# 0122-lion-charger.net
KiCad netlist of a schematic drawn in EAGLE
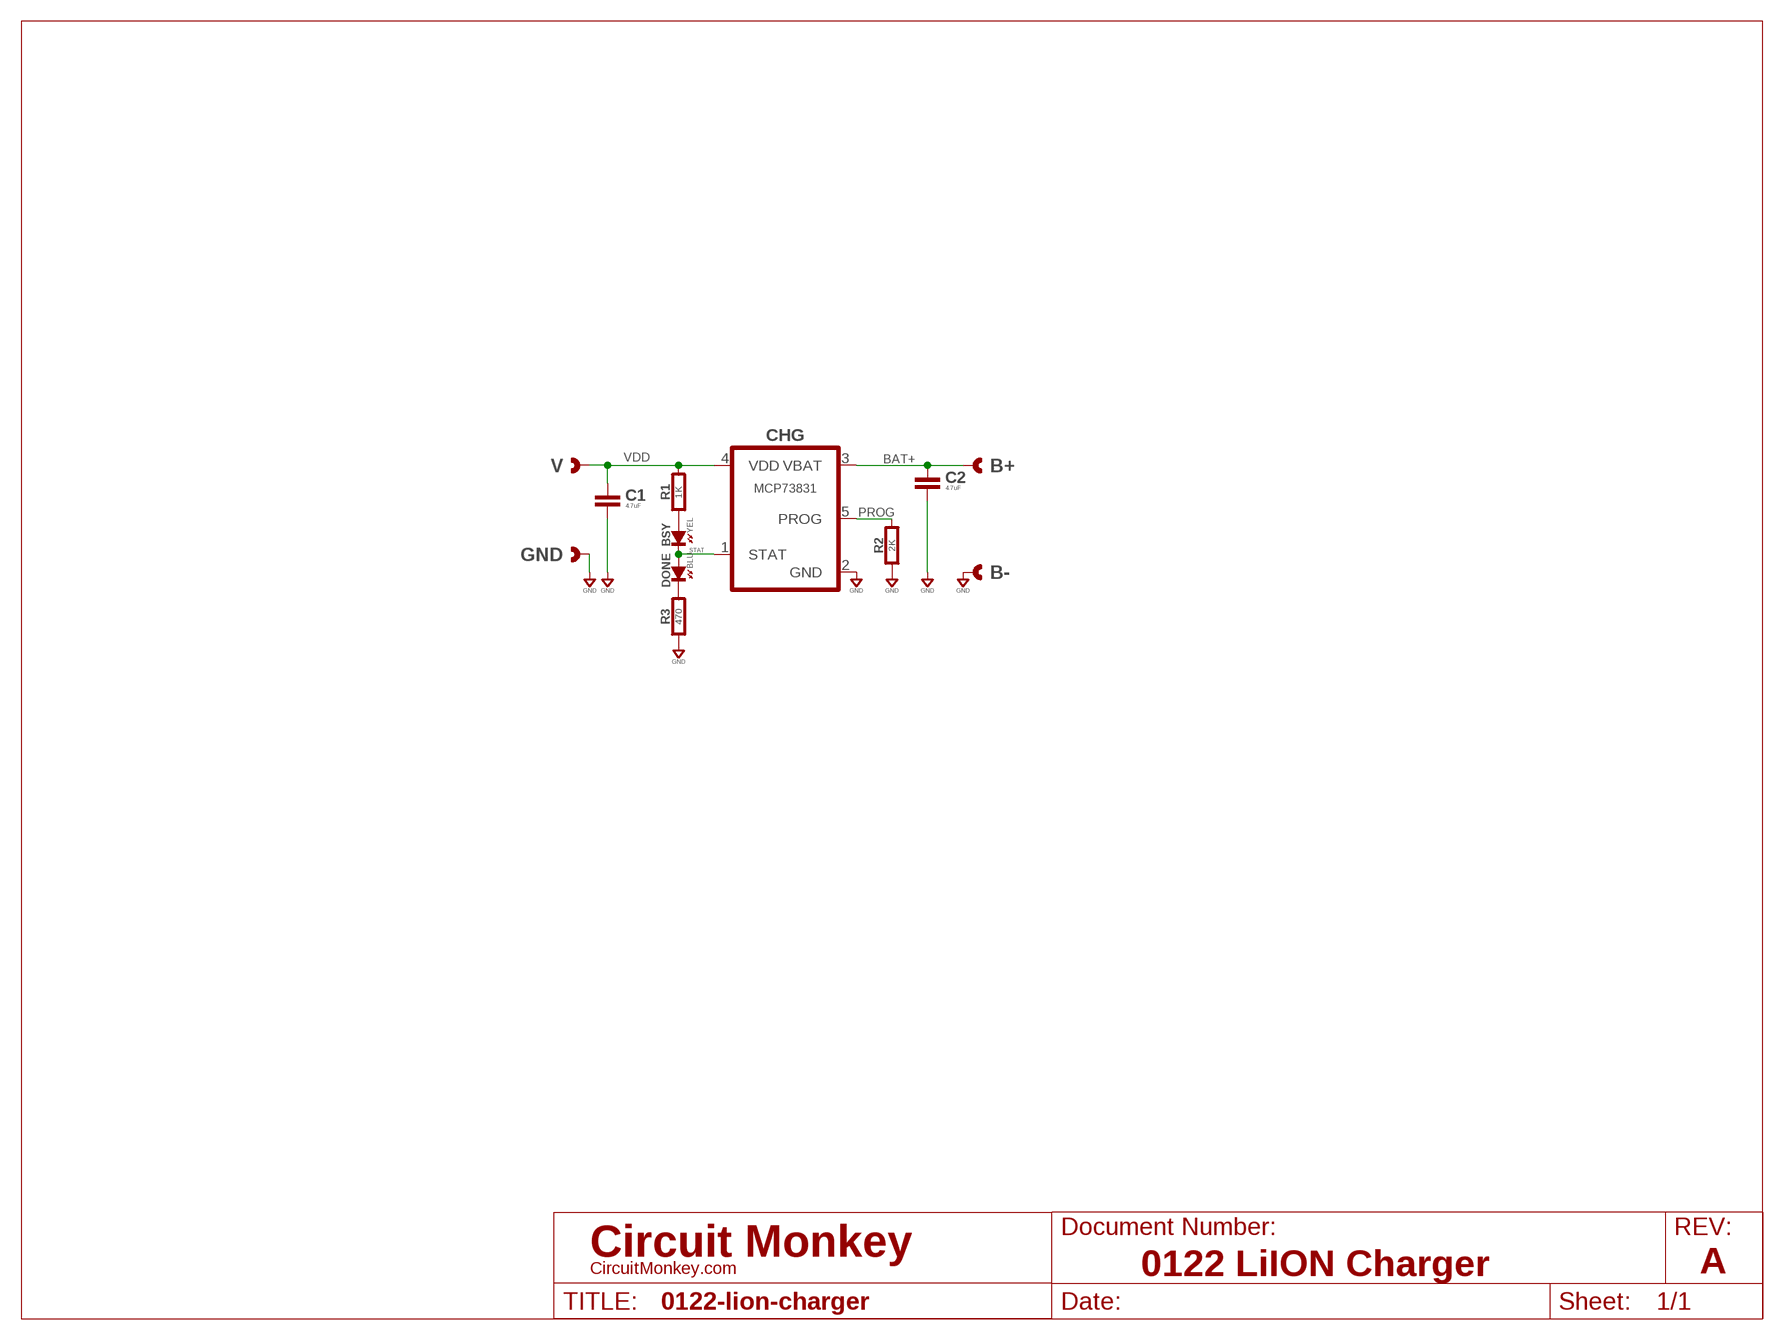
[diagram p0: schematic, sheet 1]

(export (version "E")
  (design (tool "Eeschema 10.0.6"))
  (components
    (comp (ref "B+")
      (value "CAST-01X12.00MM")
      (footprint "eagle-import:CAST01-2.00MM")
      (libsource (lib "eagle-import") (part "CAST-01X12.00MM"))
    )
    (comp (ref "B-")
      (value "CAST-01X12.00MM")
      (footprint "eagle-import:CAST01-2.00MM")
      (libsource (lib "eagle-import") (part "CAST-01X12.00MM"))
    )
    (comp (ref "BSY")
      (value "YEL")
      (footprint "eagle-import:SMD_0603")
      (libsource (lib "eagle-import") (part "SMT0603"))
    )
    (comp (ref "C1")
      (value "4.7uF")
      (footprint "eagle-import:0603-CAP")
      (libsource (lib "eagle-import") (part "CAPACITOR0603"))
    )
    (comp (ref "C2")
      (value "4.7uF")
      (footprint "eagle-import:0603-CAP")
      (libsource (lib "eagle-import") (part "CAPACITOR0603"))
    )
    (comp (ref "CHG")
      (value "MCP73831")
      (footprint "eagle-import:SOT-23-5")
      (fields (field (name "MFR") "Microchip") (field (name "MPN") "MCP73831-2ACI/OT"))
      (libsource (lib "eagle-import") (part "MCP73831/2-SOT23-5"))
    )
    (comp (ref "DONE")
      (value "BLU")
      (footprint "eagle-import:SMD_0603")
      (libsource (lib "eagle-import") (part "SMT0603"))
    )
    (comp (ref "GND")
      (value "CAST-01X12.00MM")
      (footprint "eagle-import:CAST01-2.00MM")
      (libsource (lib "eagle-import") (part "CAST-01X12.00MM"))
    )
    (comp (ref "R1")
      (value "1K")
      (footprint "eagle-import:0603-RES")
      (libsource (lib "eagle-import") (part "RESISTOR0603"))
    )
    (comp (ref "R2")
      (value "2K")
      (footprint "eagle-import:0603-RES")
      (libsource (lib "eagle-import") (part "RESISTOR0603"))
    )
    (comp (ref "R3")
      (value "470")
      (footprint "eagle-import:0603-RES")
      (libsource (lib "eagle-import") (part "RESISTOR0603"))
    )
    (comp (ref "V")
      (value "CAST-01X12.00MM")
      (footprint "eagle-import:CAST01-2.00MM")
      (libsource (lib "eagle-import") (part "CAST-01X12.00MM"))
    )
  )
  (nets
    (net (code "1") (name "/BAT+") (class "Default")
      (node (ref "B+") (pin "1") (pinfunction "1_1") (pintype "bidirectional"))
      (node (ref "B+") (pin "P$1") (pinfunction "1_P$1") (pintype "bidirectional"))
      (node (ref "B+") (pin "P$2") (pinfunction "1_P$2") (pintype "bidirectional"))
      (node (ref "C2") (pin "1") (pinfunction "1_1") (pintype "passive"))
      (node (ref "CHG") (pin "3") (pinfunction "VBAT_3") (pintype "bidirectional"))
    )
    (net (code "2") (name "/PROG") (class "Default")
      (node (ref "CHG") (pin "5") (pinfunction "PROG_5") (pintype "bidirectional"))
      (node (ref "R2") (pin "2") (pinfunction "2_2") (pintype "passive"))
    )
    (net (code "3") (name "/STAT") (class "Default")
      (node (ref "BSY") (pin "K") (pinfunction "C_K") (pintype "passive"))
      (node (ref "CHG") (pin "1") (pinfunction "STAT_1") (pintype "bidirectional"))
      (node (ref "DONE") (pin "A") (pinfunction "A_A") (pintype "passive"))
    )
    (net (code "4") (name "/VDD") (class "Default")
      (node (ref "C1") (pin "1") (pinfunction "1_1") (pintype "passive"))
      (node (ref "CHG") (pin "4") (pinfunction "VDD_4") (pintype "bidirectional"))
      (node (ref "R1") (pin "2") (pinfunction "2_2") (pintype "passive"))
      (node (ref "V") (pin "1") (pinfunction "1_1") (pintype "bidirectional"))
      (node (ref "V") (pin "P$1") (pinfunction "1_P$1") (pintype "bidirectional"))
      (node (ref "V") (pin "P$2") (pinfunction "1_P$2") (pintype "bidirectional"))
    )
    (net (code "5") (name "GND") (class "Default")
      (node (ref "B-") (pin "1") (pinfunction "1_1") (pintype "bidirectional"))
      (node (ref "B-") (pin "P$1") (pinfunction "1_P$1") (pintype "bidirectional"))
      (node (ref "B-") (pin "P$2") (pinfunction "1_P$2") (pintype "bidirectional"))
      (node (ref "C1") (pin "2") (pinfunction "2_2") (pintype "passive"))
      (node (ref "C2") (pin "2") (pinfunction "2_2") (pintype "passive"))
      (node (ref "CHG") (pin "2") (pinfunction "GND_2") (pintype "bidirectional"))
      (node (ref "GND") (pin "1") (pinfunction "1_1") (pintype "bidirectional"))
      (node (ref "GND") (pin "P$1") (pinfunction "1_P$1") (pintype "bidirectional"))
      (node (ref "GND") (pin "P$2") (pinfunction "1_P$2") (pintype "bidirectional"))
      (node (ref "R2") (pin "1") (pinfunction "1_1") (pintype "passive"))
      (node (ref "R3") (pin "1") (pinfunction "1_1") (pintype "passive"))
    )
    (net (code "6") (name "Net-(BSY-PadA)") (class "Default")
      (node (ref "BSY") (pin "A") (pinfunction "A_A") (pintype "passive"))
      (node (ref "R1") (pin "1") (pinfunction "1_1") (pintype "passive"))
    )
    (net (code "7") (name "Net-(DONE-C)") (class "Default")
      (node (ref "DONE") (pin "K") (pinfunction "C_K") (pintype "passive"))
      (node (ref "R3") (pin "2") (pinfunction "2_2") (pintype "passive"))
    )
  )
)
